# OZ440-SE100-CAR003_sheet3.net
KiCad netlist of a schematic drawn in Altium Designer
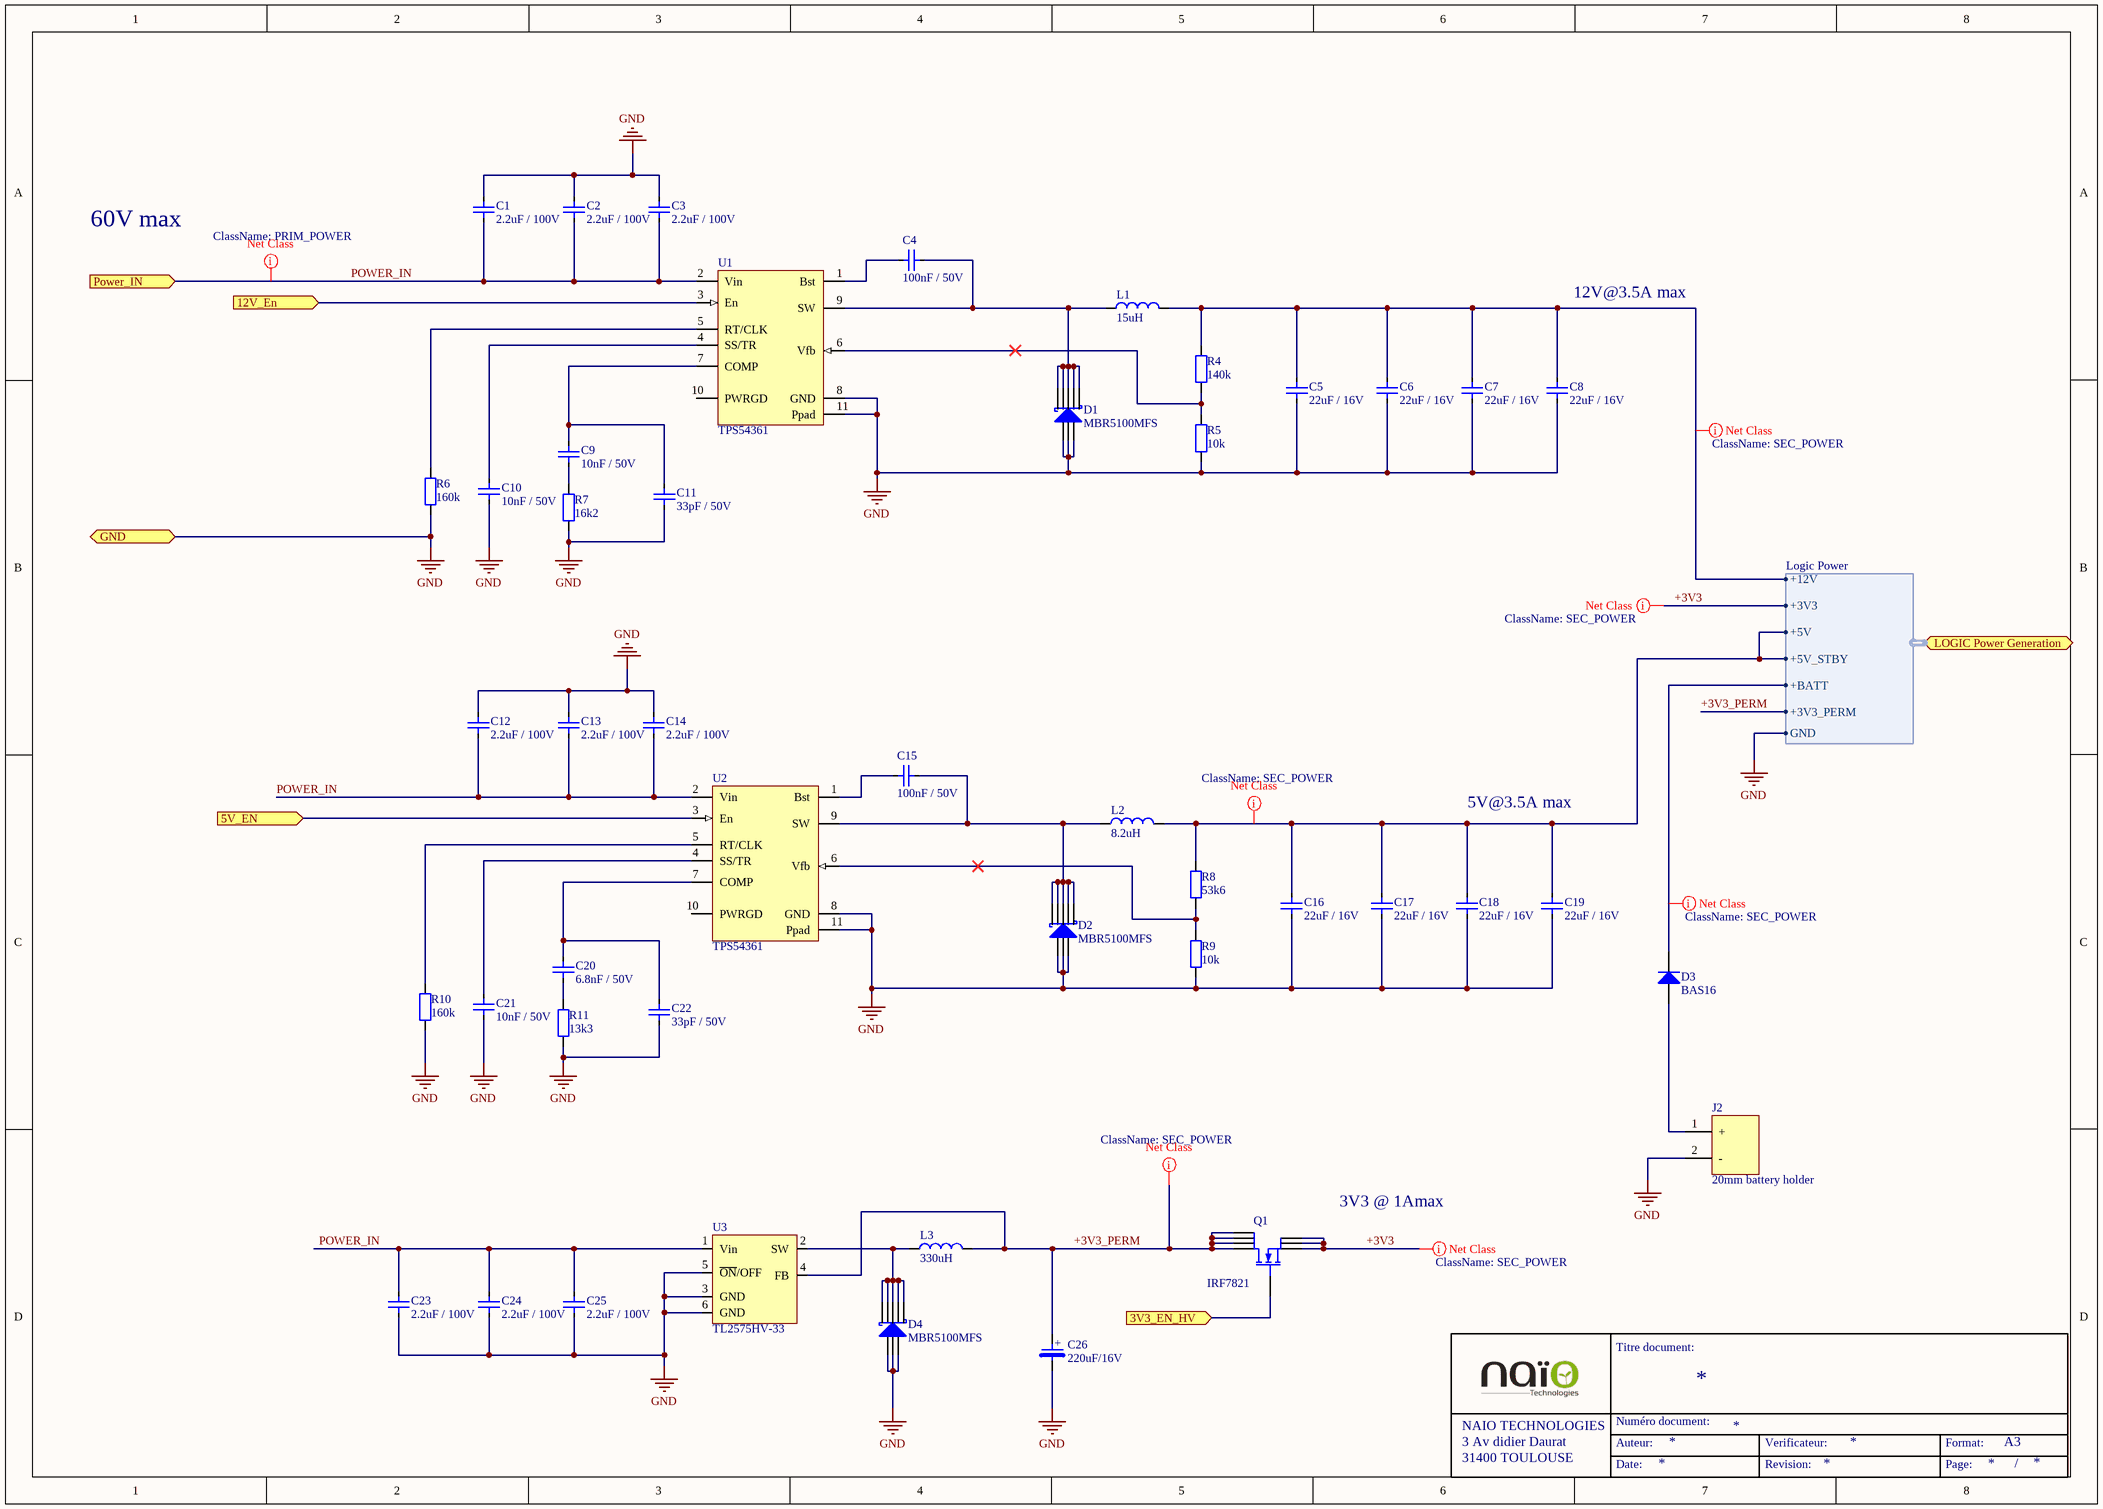
[diagram p0: OZ440-SE100-CAR003_sheet3.SchDoc]

(export (version "E")
  (design (tool "Eeschema 10.0.6"))
  (components
    (comp (ref "C1")
      (value "CAP-SMD")
      (footprint "C1206-STD")
      (description "1206 2.2uF / 100V X7S ceramic capacitor")
      (fields
        (field (name "DISPLAYED REFERENCE") "2.2uF / 100V")
        (field (name "TOLERANCE") "+/- 10%")
        (field (name "MANUFACTURER") "TDK")
      )
      (libsource (lib "lib_NAIO") (part "CAP-SMD"))
    )
    (comp (ref "C2")
      (value "CAP-SMD")
      (footprint "C1206-STD")
      (description "1206 2.2uF / 100V X7S ceramic capacitor")
      (fields
        (field (name "DISPLAYED REFERENCE") "2.2uF / 100V")
        (field (name "TOLERANCE") "+/- 10%")
        (field (name "MANUFACTURER") "TDK")
      )
      (libsource (lib "lib_NAIO") (part "CAP-SMD"))
    )
    (comp (ref "C3")
      (value "CAP-SMD")
      (footprint "C1206-STD")
      (description "1206 2.2uF / 100V X7S ceramic capacitor")
      (fields
        (field (name "DISPLAYED REFERENCE") "2.2uF / 100V")
        (field (name "TOLERANCE") "+/- 10%")
        (field (name "MANUFACTURER") "TDK")
      )
      (libsource (lib "lib_NAIO") (part "CAP-SMD"))
    )
    (comp (ref "C4")
      (value "CAP-SMD")
      (footprint "C0805-STD")
      (description "0805 100nF / 50V  X7R ceramic capacitor")
      (fields
        (field (name "DISPLAYED REFERENCE") "100nF / 50V")
        (field (name "TOLERANCE") "+/- 10%")
        (field (name "MANUFACTURER") "vishay")
      )
      (libsource (lib "lib_NAIO") (part "CAP-SMD"))
    )
    (comp (ref "C5")
      (value "CAP-SMD")
      (footprint "C1210-STD")
      (description "1210 22uF / 16V X7R ceramic capacitor")
      (fields
        (field (name "DISPLAYED REFERENCE") "22uF / 16V")
        (field (name "TOLERANCE") "+/- 10%")
        (field (name "MANUFACTURER") "AVX")
      )
      (libsource (lib "lib_NAIO") (part "CAP-SMD"))
    )
    (comp (ref "C6")
      (value "CAP-SMD")
      (footprint "C1210-STD")
      (description "1210 22uF / 16V X7R ceramic capacitor")
      (fields
        (field (name "DISPLAYED REFERENCE") "22uF / 16V")
        (field (name "TOLERANCE") "+/- 10%")
        (field (name "MANUFACTURER") "AVX")
      )
      (libsource (lib "lib_NAIO") (part "CAP-SMD"))
    )
    (comp (ref "C7")
      (value "CAP-SMD")
      (footprint "C1210-STD")
      (description "1210 22uF / 16V X7R ceramic capacitor")
      (fields
        (field (name "DISPLAYED REFERENCE") "22uF / 16V")
        (field (name "TOLERANCE") "+/- 10%")
        (field (name "MANUFACTURER") "AVX")
      )
      (libsource (lib "lib_NAIO") (part "CAP-SMD"))
    )
    (comp (ref "C8")
      (value "CAP-SMD")
      (footprint "C1210-STD")
      (description "1210 22uF / 16V X7R ceramic capacitor")
      (fields
        (field (name "DISPLAYED REFERENCE") "22uF / 16V")
        (field (name "TOLERANCE") "+/- 10%")
        (field (name "MANUFACTURER") "AVX")
      )
      (libsource (lib "lib_NAIO") (part "CAP-SMD"))
    )
    (comp (ref "C9")
      (value "CAP-SMD")
      (footprint "C0805-STD")
      (description "0805 10nF / 50V X7R ceramic capacitor")
      (fields
        (field (name "DISPLAYED REFERENCE") "10nF / 50V")
        (field (name "TOLERANCE") "+/- 10%")
        (field (name "MANUFACTURER") "vishay")
      )
      (libsource (lib "lib_NAIO") (part "CAP-SMD"))
    )
    (comp (ref "C10")
      (value "CAP-SMD")
      (footprint "C0805-STD")
      (description "0805 10nF / 50V X7R ceramic capacitor")
      (fields
        (field (name "DISPLAYED REFERENCE") "10nF / 50V")
        (field (name "TOLERANCE") "+/- 10%")
        (field (name "MANUFACTURER") "vishay")
      )
      (libsource (lib "lib_NAIO") (part "CAP-SMD"))
    )
    (comp (ref "C11")
      (value "CAP-SMD")
      (footprint "C0805-STD")
      (description "0805 33pF / 50V COG ceramic capacitor")
      (fields
        (field (name "DISPLAYED REFERENCE") "33pF / 50V")
        (field (name "TOLERANCE") "+/- 10%")
        (field (name "MANUFACTURER") "Kemet")
      )
      (libsource (lib "lib_NAIO") (part "CAP-SMD"))
    )
    (comp (ref "C12")
      (value "CAP-SMD")
      (footprint "C1206-STD")
      (description "1206 2.2uF / 100V X7S ceramic capacitor")
      (fields
        (field (name "DISPLAYED REFERENCE") "2.2uF / 100V")
        (field (name "TOLERANCE") "+/- 10%")
        (field (name "MANUFACTURER") "TDK")
      )
      (libsource (lib "lib_NAIO") (part "CAP-SMD"))
    )
    (comp (ref "C13")
      (value "CAP-SMD")
      (footprint "C1206-STD")
      (description "1206 2.2uF / 100V X7S ceramic capacitor")
      (fields
        (field (name "DISPLAYED REFERENCE") "2.2uF / 100V")
        (field (name "TOLERANCE") "+/- 10%")
        (field (name "MANUFACTURER") "TDK")
      )
      (libsource (lib "lib_NAIO") (part "CAP-SMD"))
    )
    (comp (ref "C14")
      (value "CAP-SMD")
      (footprint "C1206-STD")
      (description "1206 2.2uF / 100V X7S ceramic capacitor")
      (fields
        (field (name "DISPLAYED REFERENCE") "2.2uF / 100V")
        (field (name "TOLERANCE") "+/- 10%")
        (field (name "MANUFACTURER") "TDK")
      )
      (libsource (lib "lib_NAIO") (part "CAP-SMD"))
    )
    (comp (ref "C15")
      (value "CAP-SMD")
      (footprint "C0805-STD")
      (description "0805 100nF / 50V  X7R ceramic capacitor")
      (fields
        (field (name "DISPLAYED REFERENCE") "100nF / 50V")
        (field (name "TOLERANCE") "+/- 10%")
        (field (name "MANUFACTURER") "vishay")
      )
      (libsource (lib "lib_NAIO") (part "CAP-SMD"))
    )
    (comp (ref "C16")
      (value "CAP-SMD")
      (footprint "C1210-STD")
      (description "1210 22uF / 16V X7R ceramic capacitor")
      (fields
        (field (name "DISPLAYED REFERENCE") "22uF / 16V")
        (field (name "TOLERANCE") "+/- 10%")
        (field (name "MANUFACTURER") "AVX")
      )
      (libsource (lib "lib_NAIO") (part "CAP-SMD"))
    )
    (comp (ref "C17")
      (value "CAP-SMD")
      (footprint "C1210-STD")
      (description "1210 22uF / 16V X7R ceramic capacitor")
      (fields
        (field (name "DISPLAYED REFERENCE") "22uF / 16V")
        (field (name "TOLERANCE") "+/- 10%")
        (field (name "MANUFACTURER") "AVX")
      )
      (libsource (lib "lib_NAIO") (part "CAP-SMD"))
    )
    (comp (ref "C18")
      (value "CAP-SMD")
      (footprint "C1210-STD")
      (description "1210 22uF / 16V X7R ceramic capacitor")
      (fields
        (field (name "DISPLAYED REFERENCE") "22uF / 16V")
        (field (name "TOLERANCE") "+/- 10%")
        (field (name "MANUFACTURER") "AVX")
      )
      (libsource (lib "lib_NAIO") (part "CAP-SMD"))
    )
    (comp (ref "C19")
      (value "CAP-SMD")
      (footprint "C1210-STD")
      (description "1210 22uF / 16V X7R ceramic capacitor")
      (fields
        (field (name "DISPLAYED REFERENCE") "22uF / 16V")
        (field (name "TOLERANCE") "+/- 10%")
        (field (name "MANUFACTURER") "AVX")
      )
      (libsource (lib "lib_NAIO") (part "CAP-SMD"))
    )
    (comp (ref "C20")
      (value "CAP-SMD")
      (footprint "C0805-STD")
      (description "0805 6.8nF / 50V COG ceramic capacitor")
      (fields
        (field (name "DISPLAYED REFERENCE") "6.8nF / 50V")
        (field (name "TOLERANCE") "+/- 5%")
        (field (name "MANUFACTURER") "Kemet")
      )
      (libsource (lib "lib_NAIO") (part "CAP-SMD"))
    )
    (comp (ref "C21")
      (value "CAP-SMD")
      (footprint "C0805-STD")
      (description "0805 10nF / 50V X7R ceramic capacitor")
      (fields
        (field (name "DISPLAYED REFERENCE") "10nF / 50V")
        (field (name "TOLERANCE") "+/- 10%")
        (field (name "MANUFACTURER") "vishay")
      )
      (libsource (lib "lib_NAIO") (part "CAP-SMD"))
    )
    (comp (ref "C22")
      (value "CAP-SMD")
      (footprint "C0805-STD")
      (description "0805 33pF / 50V COG ceramic capacitor")
      (fields
        (field (name "DISPLAYED REFERENCE") "33pF / 50V")
        (field (name "TOLERANCE") "+/- 10%")
        (field (name "MANUFACTURER") "Kemet")
      )
      (libsource (lib "lib_NAIO") (part "CAP-SMD"))
    )
    (comp (ref "C23")
      (value "CAP-SMD")
      (footprint "C1206-STD")
      (description "1206 2.2uF / 100V X7S ceramic capacitor")
      (fields
        (field (name "DISPLAYED REFERENCE") "2.2uF / 100V")
        (field (name "TOLERANCE") "+/- 10%")
        (field (name "MANUFACTURER") "TDK")
      )
      (libsource (lib "lib_NAIO") (part "CAP-SMD"))
    )
    (comp (ref "C24")
      (value "CAP-SMD")
      (footprint "C1206-STD")
      (description "1206 2.2uF / 100V X7S ceramic capacitor")
      (fields
        (field (name "DISPLAYED REFERENCE") "2.2uF / 100V")
        (field (name "TOLERANCE") "+/- 10%")
        (field (name "MANUFACTURER") "TDK")
      )
      (libsource (lib "lib_NAIO") (part "CAP-SMD"))
    )
    (comp (ref "C25")
      (value "CAP-SMD")
      (footprint "C1206-STD")
      (description "1206 2.2uF / 100V X7S ceramic capacitor")
      (fields
        (field (name "DISPLAYED REFERENCE") "2.2uF / 100V")
        (field (name "TOLERANCE") "+/- 10%")
        (field (name "MANUFACTURER") "TDK")
      )
      (libsource (lib "lib_NAIO") (part "CAP-SMD"))
    )
    (comp (ref "C26")
      (value "CAP-POL-SMD")
      (footprint "CAP-ELECTRO-SMD")
      (description "220uF/16V Aluminium capacitor SMD")
      (fields (field (name "DISPLAYED REFERENCE") "220uF/16V") (field (name "MANUFACTURER") "Epcos"))
      (libsource (lib "lib_NAIO") (part "CAP-POL-SMD"))
    )
    (comp (ref "D1")
      (value "MBR5100MFS-SO8")
      (footprint "SO8-SPE-MBR5100MFS")
      (description "Power shottky Diode")
      (fields (field (name "DISPLAYED REFERENCE") "MBR5100MFS") (field (name "MANUFACTURER") "ON semi"))
      (libsource (lib "lib_NAIO") (part "MBR5100MFS-SO8"))
    )
    (comp (ref "D2")
      (value "MBR5100MFS-SO8")
      (footprint "SO8-SPE-MBR5100MFS")
      (description "Power shottky Diode")
      (fields (field (name "DISPLAYED REFERENCE") "MBR5100MFS") (field (name "MANUFACTURER") "ON semi"))
      (libsource (lib "lib_NAIO") (part "MBR5100MFS-SO8"))
    )
    (comp (ref "D3")
      (value "BAS16-SOT23")
      (footprint "SOT23-STD")
      (description "100V / 120mA signal  diode")
      (fields (field (name "DISPLAYED REFERENCE") "BAS16") (field (name "MANUFACTURER") "NXP"))
      (libsource (lib "lib_NAIO") (part "BAS16-SOT23"))
    )
    (comp (ref "D4")
      (value "MBR5100MFS-SO8")
      (footprint "SO8-SPE-MBR5100MFS")
      (description "Power shottky Diode")
      (fields (field (name "DISPLAYED REFERENCE") "MBR5100MFS") (field (name "MANUFACTURER") "ON semi"))
      (libsource (lib "lib_NAIO") (part "MBR5100MFS-SO8"))
    )
    (comp (ref "J2")
      (value "CONN-STD-2P_BATTERY")
      (footprint "CONN-SPE-Keyst_1081")
      (description "20mm battery Holder, SMT")
      (fields
        (field (name "DISPLAYED REFERENCE") "20mm battery holder")
        (field (name "MANUFACTURER") "Keystone")
      )
      (libsource (lib "lib_NAIO") (part "CONN-STD-2P_BATTERY"))
    )
    (comp (ref "L1")
      (value "IND-SMD")
      (footprint "L-SPE-XAL60xx")
      (description "15uH SMD inductor")
      (fields (field (name "DISPLAYED REFERENCE") "15uH") (field (name "MANUFACTURER") "COILCRAFT"))
      (libsource (lib "lib_NAIO") (part "IND-SMD"))
    )
    (comp (ref "L2")
      (value "IND-SMD")
      (footprint "L-SPE-XAL60xx")
      (description "8.2uH SMD inductor")
      (fields (field (name "DISPLAYED REFERENCE") "8.2uH") (field (name "MANUFACTURER") "COILCRAFT"))
      (libsource (lib "lib_NAIO") (part "IND-SMD"))
    )
    (comp (ref "L3")
      (value "IND-SMD")
      (footprint "L-SPE-MSS1260")
      (description "330uH SMD inductor")
      (fields (field (name "DISPLAYED REFERENCE") "330uH") (field (name "MANUFACTURER") "COILCRAFT"))
      (libsource (lib "lib_NAIO") (part "IND-SMD"))
    )
    (comp (ref "Q1")
      (value "IRF7832-SO8")
      (footprint "SO8-SPE-IRF7832")
      (description "11A N channel MOSFET in SO08 package")
      (fields (field (name "DISPLAYED REFERENCE") "IRF7821") (field (name "MANUFACTURER") "IRF"))
      (libsource (lib "lib_NAIO") (part "IRF7832-SO8"))
    )
    (comp (ref "R4")
      (value "RES-SMD")
      (footprint "R0805-STD")
      (description "140k Ohm 0805 SMD resistor")
      (fields
        (field (name "DISPLAYED REFERENCE") "140k")
        (field (name "TOLERANCE") "1%")
        (field (name "MANUFACTURER") "Vishay")
      )
      (libsource (lib "lib_NAIO") (part "RES-SMD"))
    )
    (comp (ref "R5")
      (value "RES-SMD")
      (footprint "R0805-STD")
      (description "10k Ohm 0805 SMD resistor")
      (fields
        (field (name "DISPLAYED REFERENCE") "10k")
        (field (name "TOLERANCE") "1 %")
        (field (name "MANUFACTURER") "Vishay")
      )
      (libsource (lib "lib_NAIO") (part "RES-SMD"))
    )
    (comp (ref "R6")
      (value "RES-SMD")
      (footprint "R0805-STD")
      (description "160k Ohm 0805 SMD resistor")
      (fields
        (field (name "DISPLAYED REFERENCE") "160k")
        (field (name "TOLERANCE") "1%")
        (field (name "MANUFACTURER") "Vishay")
      )
      (libsource (lib "") (part "RES-SMD_1"))
    )
    (comp (ref "R7")
      (value "RES-SMD")
      (footprint "R0805-STD")
      (description "16k2 Ohm 0805 SMD resistor")
      (fields
        (field (name "DISPLAYED REFERENCE") "16k2")
        (field (name "TOLERANCE") "1%")
        (field (name "MANUFACTURER") "Vishay")
      )
      (libsource (lib "lib_NAIO") (part "RES-SMD"))
    )
    (comp (ref "R8")
      (value "RES-SMD")
      (footprint "R0805-STD")
      (description "53k6 Ohm 0805 SMD resistor")
      (fields
        (field (name "DISPLAYED REFERENCE") "53k6")
        (field (name "TOLERANCE") "1%")
        (field (name "MANUFACTURER") "Vishay")
      )
      (libsource (lib "lib_NAIO") (part "RES-SMD"))
    )
    (comp (ref "R9")
      (value "RES-SMD")
      (footprint "R0805-STD")
      (description "10k Ohm 0805 SMD resistor")
      (fields
        (field (name "DISPLAYED REFERENCE") "10k")
        (field (name "TOLERANCE") "1 %")
        (field (name "MANUFACTURER") "Vishay")
      )
      (libsource (lib "lib_NAIO") (part "RES-SMD"))
    )
    (comp (ref "R10")
      (value "RES-SMD")
      (footprint "R0805-STD")
      (description "160k Ohm 0805 SMD resistor")
      (fields
        (field (name "DISPLAYED REFERENCE") "160k")
        (field (name "TOLERANCE") "1%")
        (field (name "MANUFACTURER") "Vishay")
      )
      (libsource (lib "") (part "RES-SMD_1"))
    )
    (comp (ref "R11")
      (value "RES-SMD")
      (footprint "R0805-STD")
      (description "13k3 Ohm 0805 SMD resistor")
      (fields
        (field (name "DISPLAYED REFERENCE") "13k3")
        (field (name "TOLERANCE") "1%")
        (field (name "MANUFACTURER") "Vishay")
      )
      (libsource (lib "lib_NAIO") (part "RES-SMD"))
    )
    (comp (ref "U1")
      (value "TPS54361-SON10")
      (footprint "SON10-SPE-TPS54361")
      (description "4.5-V to 60-V Input, 3.5-A, Step Down DC-DC Converter")
      (fields (field (name "DISPLAYED REFERENCE") "TPS54361") (field (name "MANUFACTURER") "TI"))
      (libsource (lib "lib_NAIO") (part "TPS54361-SON10"))
    )
    (comp (ref "U2")
      (value "TPS54361-SON10")
      (footprint "SON10-SPE-TPS54361")
      (description "4.5-V to 60-V Input, 3.5-A, Step Down DC-DC Converter")
      (fields (field (name "DISPLAYED REFERENCE") "TPS54361") (field (name "MANUFACTURER") "TI"))
      (libsource (lib "lib_NAIO") (part "TPS54361-SON10"))
    )
    (comp (ref "U3")
      (value "TL2575HV-xx-TO263")
      (footprint "TO263-5-SPE-TL2575HV")
      (description "1-A SIMPLE STEP-DOWN VOLTAGE REGULATOR")
      (fields (field (name "DISPLAYED REFERENCE") "TL2575HV-33") (field (name "MANUFACTURER") "TI"))
      (libsource (lib "lib_NAIO") (part "TL2575HV-xx-TO263"))
    )
  )
  (nets
    (net (code "3") (name "/+3V3") (class "Default")
      (node (ref "Q1") (pin "1") (pinfunction "S_1") (pintype "passive"))
      (node (ref "Q1") (pin "2") (pinfunction "S_2") (pintype "passive"))
      (node (ref "Q1") (pin "3") (pinfunction "S_3") (pintype "passive"))
    )
    (net (code "4") (name "/+3V3_PERM") (class "Default")
      (node (ref "C26") (pin "1") (pinfunction "1_1") (pintype "passive"))
      (node (ref "L3") (pin "2") (pinfunction "2_2") (pintype "passive"))
      (node (ref "Q1") (pin "5") (pinfunction "D_5") (pintype "passive"))
      (node (ref "Q1") (pin "6") (pinfunction "D_6") (pintype "passive"))
      (node (ref "Q1") (pin "7") (pinfunction "D_7") (pintype "passive"))
      (node (ref "Q1") (pin "8") (pinfunction "D_8") (pintype "passive"))
      (node (ref "U3") (pin "4") (pinfunction "FB_4") (pintype "passive"))
    )
    (net (code "5") (name "/+5V") (class "Default")
      (node (ref "C16") (pin "2") (pinfunction "2_2") (pintype "passive"))
      (node (ref "C17") (pin "2") (pinfunction "2_2") (pintype "passive"))
      (node (ref "C18") (pin "2") (pinfunction "2_2") (pintype "passive"))
      (node (ref "C19") (pin "2") (pinfunction "2_2") (pintype "passive"))
      (node (ref "L2") (pin "2") (pinfunction "2_2") (pintype "passive"))
      (node (ref "R8") (pin "2") (pinfunction "2_2") (pintype "passive"))
    )
    (net (code "6") (name "/+12V") (class "Default")
      (node (ref "C5") (pin "2") (pinfunction "2_2") (pintype "passive"))
      (node (ref "C6") (pin "2") (pinfunction "2_2") (pintype "passive"))
      (node (ref "C7") (pin "2") (pinfunction "2_2") (pintype "passive"))
      (node (ref "C8") (pin "2") (pinfunction "2_2") (pintype "passive"))
      (node (ref "L1") (pin "2") (pinfunction "2_2") (pintype "passive"))
      (node (ref "R4") (pin "2") (pinfunction "2_2") (pintype "passive"))
    )
    (net (code "7") (name "/+BATT") (class "Default")
      (node (ref "D3") (pin "3") (pinfunction "K_3") (pintype "passive"))
    )
    (net (code "8") (name "/3V3_EN_HV") (class "Default")
      (node (ref "Q1") (pin "4") (pinfunction "G_4") (pintype "passive"))
    )
    (net (code "9") (name "/5V_EN") (class "Default")
      (node (ref "U2") (pin "3") (pinfunction "En_3") (pintype "input"))
    )
    (net (code "10") (name "/12V_En") (class "Default")
      (node (ref "U1") (pin "3") (pinfunction "En_3") (pintype "input"))
    )
    (net (code "11") (name "/POWER_IN") (class "Default")
      (node (ref "C1") (pin "1") (pinfunction "1_1") (pintype "passive"))
      (node (ref "C12") (pin "1") (pinfunction "1_1") (pintype "passive"))
      (node (ref "C13") (pin "1") (pinfunction "1_1") (pintype "passive"))
      (node (ref "C14") (pin "1") (pinfunction "1_1") (pintype "passive"))
      (node (ref "C2") (pin "1") (pinfunction "1_1") (pintype "passive"))
      (node (ref "C23") (pin "2") (pinfunction "2_2") (pintype "passive"))
      (node (ref "C24") (pin "2") (pinfunction "2_2") (pintype "passive"))
      (node (ref "C25") (pin "2") (pinfunction "2_2") (pintype "passive"))
      (node (ref "C3") (pin "1") (pinfunction "1_1") (pintype "passive"))
      (node (ref "U1") (pin "2") (pinfunction "Vin_2") (pintype "passive"))
      (node (ref "U2") (pin "2") (pinfunction "Vin_2") (pintype "passive"))
      (node (ref "U3") (pin "1") (pinfunction "Vin_1") (pintype "passive"))
    )
    (net (code "13") (name "GND") (class "Default")
      (node (ref "C1") (pin "2") (pinfunction "2_2") (pintype "passive"))
      (node (ref "C10") (pin "1") (pinfunction "1_1") (pintype "passive"))
      (node (ref "C11") (pin "1") (pinfunction "1_1") (pintype "passive"))
      (node (ref "C12") (pin "2") (pinfunction "2_2") (pintype "passive"))
      (node (ref "C13") (pin "2") (pinfunction "2_2") (pintype "passive"))
      (node (ref "C14") (pin "2") (pinfunction "2_2") (pintype "passive"))
      (node (ref "C16") (pin "1") (pinfunction "1_1") (pintype "passive"))
      (node (ref "C17") (pin "1") (pinfunction "1_1") (pintype "passive"))
      (node (ref "C18") (pin "1") (pinfunction "1_1") (pintype "passive"))
      (node (ref "C19") (pin "1") (pinfunction "1_1") (pintype "passive"))
      (node (ref "C2") (pin "2") (pinfunction "2_2") (pintype "passive"))
      (node (ref "C21") (pin "1") (pinfunction "1_1") (pintype "passive"))
      (node (ref "C22") (pin "1") (pinfunction "1_1") (pintype "passive"))
      (node (ref "C23") (pin "1") (pinfunction "1_1") (pintype "passive"))
      (node (ref "C24") (pin "1") (pinfunction "1_1") (pintype "passive"))
      (node (ref "C25") (pin "1") (pinfunction "1_1") (pintype "passive"))
      (node (ref "C26") (pin "2") (pinfunction "2_2") (pintype "passive"))
      (node (ref "C3") (pin "2") (pinfunction "2_2") (pintype "passive"))
      (node (ref "C5") (pin "1") (pinfunction "1_1") (pintype "passive"))
      (node (ref "C6") (pin "1") (pinfunction "1_1") (pintype "passive"))
      (node (ref "C7") (pin "1") (pinfunction "1_1") (pintype "passive"))
      (node (ref "C8") (pin "1") (pinfunction "1_1") (pintype "passive"))
      (node (ref "D1") (pin "1") (pinfunction "A_1") (pintype "passive"))
      (node (ref "D1") (pin "2") (pinfunction "A_2") (pintype "passive"))
      (node (ref "D1") (pin "3") (pinfunction "A_3") (pintype "passive"))
      (node (ref "D2") (pin "1") (pinfunction "A_1") (pintype "passive"))
      (node (ref "D2") (pin "2") (pinfunction "A_2") (pintype "passive"))
      (node (ref "D2") (pin "3") (pinfunction "A_3") (pintype "passive"))
      (node (ref "D4") (pin "1") (pinfunction "A_1") (pintype "passive"))
      (node (ref "D4") (pin "2") (pinfunction "A_2") (pintype "passive"))
      (node (ref "D4") (pin "3") (pinfunction "A_3") (pintype "passive"))
      (node (ref "J2") (pin "2") (pinfunction "-_2") (pintype "passive"))
      (node (ref "R10") (pin "2") (pinfunction "2_2") (pintype "passive"))
      (node (ref "R11") (pin "1") (pinfunction "1_1") (pintype "passive"))
      (node (ref "R5") (pin "1") (pinfunction "1_1") (pintype "passive"))
      (node (ref "R6") (pin "2") (pinfunction "2_2") (pintype "passive"))
      (node (ref "R7") (pin "1") (pinfunction "1_1") (pintype "passive"))
      (node (ref "R9") (pin "1") (pinfunction "1_1") (pintype "passive"))
      (node (ref "U1") (pin "11") (pinfunction "Ppad_11") (pintype "passive"))
      (node (ref "U1") (pin "8") (pinfunction "GND_8") (pintype "passive"))
      (node (ref "U2") (pin "11") (pinfunction "Ppad_11") (pintype "passive"))
      (node (ref "U2") (pin "8") (pinfunction "GND_8") (pintype "passive"))
      (node (ref "U3") (pin "3") (pinfunction "GND_3") (pintype "passive"))
      (node (ref "U3") (pin "5") (pinfunction "~{ON}/OFF_5") (pintype "passive"))
      (node (ref "U3") (pin "6") (pinfunction "GND_6") (pintype "passive"))
    )
    (net (code "14") (name "Net-(C9-Pad1)") (class "Default")
      (node (ref "C9") (pin "1") (pinfunction "1_1") (pintype "passive"))
      (node (ref "R7") (pin "2") (pinfunction "2_2") (pintype "passive"))
    )
    (net (code "15") (name "Net-(C20-Pad1)") (class "Default")
      (node (ref "C20") (pin "1") (pinfunction "1_1") (pintype "passive"))
      (node (ref "R11") (pin "2") (pinfunction "2_2") (pintype "passive"))
    )
    (net (code "16") (name "Net-(D3-A)") (class "Default")
      (node (ref "D3") (pin "1") (pinfunction "A_1") (pintype "passive"))
      (node (ref "J2") (pin "1") (pinfunction "+_1") (pintype "passive"))
    )
    (net (code "17") (name "Net-(U1-Bst)") (class "Default")
      (node (ref "C4") (pin "1") (pinfunction "1_1") (pintype "passive"))
      (node (ref "U1") (pin "1") (pinfunction "Bst_1") (pintype "passive"))
    )
    (net (code "18") (name "Net-(U1-COMP)") (class "Default")
      (node (ref "C11") (pin "2") (pinfunction "2_2") (pintype "passive"))
      (node (ref "C9") (pin "2") (pinfunction "2_2") (pintype "passive"))
      (node (ref "U1") (pin "7") (pinfunction "COMP_7") (pintype "passive"))
    )
    (net (code "19") (name "Net-(U1-RT{slash}CLK)") (class "Default")
      (node (ref "R6") (pin "1") (pinfunction "1_1") (pintype "passive"))
      (node (ref "U1") (pin "5") (pinfunction "RT/CLK_5") (pintype "passive"))
    )
    (net (code "20") (name "Net-(U1-SS{slash}TR)") (class "Default")
      (node (ref "C10") (pin "2") (pinfunction "2_2") (pintype "passive"))
      (node (ref "U1") (pin "4") (pinfunction "SS/TR_4") (pintype "passive"))
    )
    (net (code "21") (name "Net-(U1-SW)") (class "Default")
      (node (ref "C4") (pin "2") (pinfunction "2_2") (pintype "passive"))
      (node (ref "D1") (pin "5") (pinfunction "K_5") (pintype "passive"))
      (node (ref "D1") (pin "6") (pinfunction "K_6") (pintype "passive"))
      (node (ref "D1") (pin "7") (pinfunction "K_7") (pintype "passive"))
      (node (ref "D1") (pin "8") (pinfunction "K_8") (pintype "passive"))
      (node (ref "L1") (pin "1") (pinfunction "1_1") (pintype "passive"))
      (node (ref "U1") (pin "9") (pinfunction "SW_9") (pintype "passive"))
    )
    (net (code "22") (name "Net-(U1-Vfb)") (class "Default")
      (node (ref "R4") (pin "1") (pinfunction "1_1") (pintype "passive"))
      (node (ref "R5") (pin "2") (pinfunction "2_2") (pintype "passive"))
      (node (ref "U1") (pin "6") (pinfunction "Vfb_6") (pintype "input"))
    )
    (net (code "23") (name "Net-(U2-Bst)") (class "Default")
      (node (ref "C15") (pin "1") (pinfunction "1_1") (pintype "passive"))
      (node (ref "U2") (pin "1") (pinfunction "Bst_1") (pintype "passive"))
    )
    (net (code "24") (name "Net-(U2-COMP)") (class "Default")
      (node (ref "C20") (pin "2") (pinfunction "2_2") (pintype "passive"))
      (node (ref "C22") (pin "2") (pinfunction "2_2") (pintype "passive"))
      (node (ref "U2") (pin "7") (pinfunction "COMP_7") (pintype "passive"))
    )
    (net (code "25") (name "Net-(U2-RT{slash}CLK)") (class "Default")
      (node (ref "R10") (pin "1") (pinfunction "1_1") (pintype "passive"))
      (node (ref "U2") (pin "5") (pinfunction "RT/CLK_5") (pintype "passive"))
    )
    (net (code "26") (name "Net-(U2-SS{slash}TR)") (class "Default")
      (node (ref "C21") (pin "2") (pinfunction "2_2") (pintype "passive"))
      (node (ref "U2") (pin "4") (pinfunction "SS/TR_4") (pintype "passive"))
    )
    (net (code "27") (name "Net-(U2-SW)") (class "Default")
      (node (ref "C15") (pin "2") (pinfunction "2_2") (pintype "passive"))
      (node (ref "D2") (pin "5") (pinfunction "K_5") (pintype "passive"))
      (node (ref "D2") (pin "6") (pinfunction "K_6") (pintype "passive"))
      (node (ref "D2") (pin "7") (pinfunction "K_7") (pintype "passive"))
      (node (ref "D2") (pin "8") (pinfunction "K_8") (pintype "passive"))
      (node (ref "L2") (pin "1") (pinfunction "1_1") (pintype "passive"))
      (node (ref "U2") (pin "9") (pinfunction "SW_9") (pintype "passive"))
    )
    (net (code "28") (name "Net-(U2-Vfb)") (class "Default")
      (node (ref "R8") (pin "1") (pinfunction "1_1") (pintype "passive"))
      (node (ref "R9") (pin "2") (pinfunction "2_2") (pintype "passive"))
      (node (ref "U2") (pin "6") (pinfunction "Vfb_6") (pintype "input"))
    )
    (net (code "29") (name "Net-(U3-SW)") (class "Default")
      (node (ref "D4") (pin "5") (pinfunction "K_5") (pintype "passive"))
      (node (ref "D4") (pin "6") (pinfunction "K_6") (pintype "passive"))
      (node (ref "D4") (pin "7") (pinfunction "K_7") (pintype "passive"))
      (node (ref "D4") (pin "8") (pinfunction "K_8") (pintype "passive"))
      (node (ref "L3") (pin "1") (pinfunction "1_1") (pintype "passive"))
      (node (ref "U3") (pin "2") (pinfunction "SW_2") (pintype "passive"))
    )
    (net (code "30") (name "unconnected-(U1-PWRGD-Pad10)") (class "Default")
      (node (ref "U1") (pin "10") (pinfunction "PWRGD_10") (pintype "open_collector"))
    )
    (net (code "31") (name "unconnected-(U2-PWRGD-Pad10)") (class "Default")
      (node (ref "U2") (pin "10") (pinfunction "PWRGD_10") (pintype "open_collector"))
    )
  )
)
